# memory.net
KiCad netlist of a schematic drawn in Altium Designer
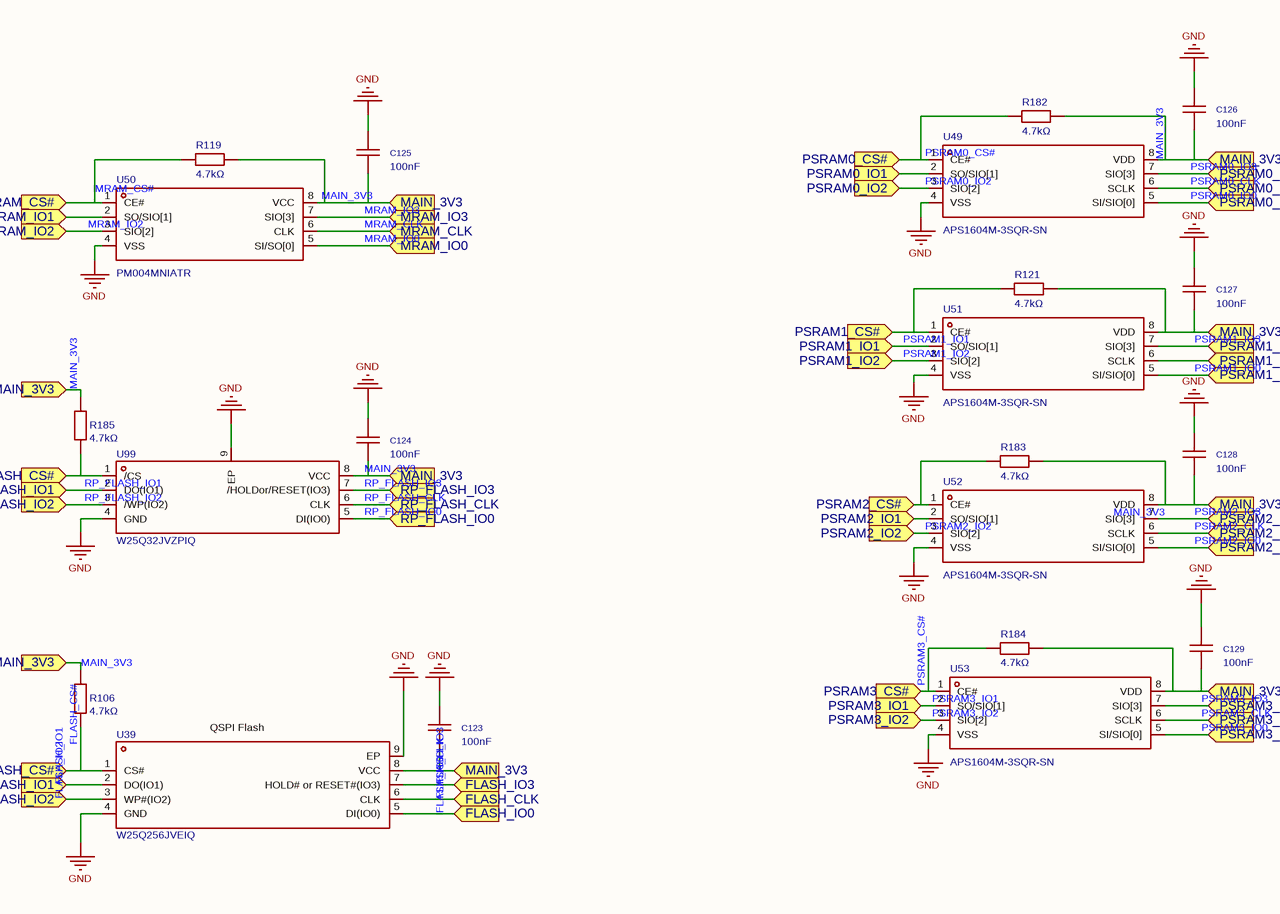
[diagram p0: memory.schdoc]

(export (version "E")
  (design (tool "Eeschema 10.0.6"))
  (components
    (comp (ref "C123")
      (value "100nF")
      (footprint "C0603")
      (description "Capacitance:22nF Tolerance:±10% Tolerance:±10% Voltage Rating:50V Temperature Coefficient:X7R")
      (fields
        (field (name "MANUFACTURER PART") "CL10B223KB8NNNC")
        (field (name "MANUFACTURER") "SAMSUNG(三星)")
      )
      (libsource (lib "altium-import") (part "root_1_CL10B223KB8NNNC_"))
    )
    (comp (ref "C124")
      (value "100nF")
      (footprint "C0603")
      (description "Capacitance:22nF Tolerance:±10% Tolerance:±10% Voltage Rating:50V Temperature Coefficient:X7R")
      (fields
        (field (name "MANUFACTURER PART") "CL10B223KB8NNNC")
        (field (name "MANUFACTURER") "SAMSUNG(三星)")
      )
      (libsource (lib "altium-import") (part "root_1_CL10B223KB8NNNC_"))
    )
    (comp (ref "C125")
      (value "100nF")
      (footprint "C0603")
      (description "Capacitance:22nF Tolerance:±10% Tolerance:±10% Voltage Rating:50V Temperature Coefficient:X7R")
      (fields
        (field (name "MANUFACTURER PART") "CL10B223KB8NNNC")
        (field (name "MANUFACTURER") "SAMSUNG(三星)")
      )
      (libsource (lib "altium-import") (part "root_1_CL10B223KB8NNNC_"))
    )
    (comp (ref "C126")
      (value "100nF")
      (footprint "C0603")
      (description "Capacitance:22nF Tolerance:±10% Tolerance:±10% Voltage Rating:50V Temperature Coefficient:X7R")
      (fields
        (field (name "MANUFACTURER PART") "CL10B223KB8NNNC")
        (field (name "MANUFACTURER") "SAMSUNG(三星)")
      )
      (libsource (lib "altium-import") (part "root_1_CL10B223KB8NNNC_"))
    )
    (comp (ref "C127")
      (value "100nF")
      (footprint "C0603")
      (description "Capacitance:22nF Tolerance:±10% Tolerance:±10% Voltage Rating:50V Temperature Coefficient:X7R")
      (fields
        (field (name "MANUFACTURER PART") "CL10B223KB8NNNC")
        (field (name "MANUFACTURER") "SAMSUNG(三星)")
      )
      (libsource (lib "altium-import") (part "root_1_CL10B223KB8NNNC_"))
    )
    (comp (ref "C128")
      (value "100nF")
      (footprint "C0603")
      (description "Capacitance:22nF Tolerance:±10% Tolerance:±10% Voltage Rating:50V Temperature Coefficient:X7R")
      (fields
        (field (name "MANUFACTURER PART") "CL10B223KB8NNNC")
        (field (name "MANUFACTURER") "SAMSUNG(三星)")
      )
      (libsource (lib "altium-import") (part "root_1_CL10B223KB8NNNC_"))
    )
    (comp (ref "C129")
      (value "100nF")
      (footprint "C0603")
      (description "Capacitance:22nF Tolerance:±10% Tolerance:±10% Voltage Rating:50V Temperature Coefficient:X7R")
      (fields
        (field (name "MANUFACTURER PART") "CL10B223KB8NNNC")
        (field (name "MANUFACTURER") "SAMSUNG(三星)")
      )
      (libsource (lib "altium-import") (part "root_1_CL10B223KB8NNNC_"))
    )
    (comp (ref "R106")
      (value "4.7kΩ")
      (footprint "R0603")
      (fields (field (name "MANUFACTURER") "YAGEO(国巨)") (field (name "MANUFACTURER PART") "RC0603FR-074K7L"))
      (libsource (lib "altium-import") (part "root_1_4.7kΩ_"))
    )
    (comp (ref "R119")
      (value "4.7kΩ")
      (footprint "R0603")
      (fields (field (name "MANUFACTURER") "YAGEO(国巨)") (field (name "MANUFACTURER PART") "RC0603FR-074K7L"))
      (libsource (lib "altium-import") (part "root_0_4.7kΩ_"))
    )
    (comp (ref "R121")
      (value "4.7kΩ")
      (footprint "R0603")
      (fields (field (name "MANUFACTURER") "YAGEO(国巨)") (field (name "MANUFACTURER PART") "RC0603FR-074K7L"))
      (libsource (lib "altium-import") (part "root_0_4.7kΩ_"))
    )
    (comp (ref "R182")
      (value "4.7kΩ")
      (footprint "R0603")
      (fields (field (name "MANUFACTURER") "YAGEO(国巨)") (field (name "MANUFACTURER PART") "RC0603FR-074K7L"))
      (libsource (lib "altium-import") (part "root_0_4.7kΩ_"))
    )
    (comp (ref "R183")
      (value "4.7kΩ")
      (footprint "R0603")
      (fields (field (name "MANUFACTURER") "YAGEO(国巨)") (field (name "MANUFACTURER PART") "RC0603FR-074K7L"))
      (libsource (lib "altium-import") (part "root_0_4.7kΩ_"))
    )
    (comp (ref "R184")
      (value "4.7kΩ")
      (footprint "R0603")
      (fields (field (name "MANUFACTURER") "YAGEO(国巨)") (field (name "MANUFACTURER PART") "RC0603FR-074K7L"))
      (libsource (lib "altium-import") (part "root_0_4.7kΩ_"))
    )
    (comp (ref "R185")
      (value "4.7kΩ")
      (footprint "R0603")
      (fields (field (name "MANUFACTURER") "YAGEO(国巨)") (field (name "MANUFACTURER PART") "RC0603FR-074K7L"))
      (libsource (lib "altium-import") (part "root_1_4.7kΩ_"))
    )
    (comp (ref "U39")
      (value "W25Q256JVEIQ")
      (footprint "WSON-8_L8.0-W6.10-P1.27-BL-EP")
      (fields (field (name "MANUFACTURER") "WINBOND(华邦)"))
      (libsource (lib "altium-import") (part "root_0_W25Q256JVEIQ_C97522_"))
    )
    (comp (ref "U49")
      (value "APS1604M-3SQR-SN")
      (footprint "SOIC-8_L4.9-W3.9-P1.27-LS6.0-BL")
      (fields (field (name "MANUFACTURER") "Apmemory"))
      (libsource (lib "altium-import") (part "root_0_APS1604M-3SQR-SN_C18214056_"))
    )
    (comp (ref "U50")
      (value "PM004MNIATR")
      (footprint "SOP-8_L4.9-W3.9-P1.27-LS6.0-BL")
      (fields (field (name "MANUFACTURER") "Siproin(上海矽朋)"))
      (libsource (lib "altium-import") (part "root_0_PM004MNIATR_"))
    )
    (comp (ref "U51")
      (value "APS1604M-3SQR-SN")
      (footprint "SOIC-8_L4.9-W3.9-P1.27-LS6.0-BL")
      (fields (field (name "MANUFACTURER") "Apmemory"))
      (libsource (lib "altium-import") (part "root_0_APS1604M-3SQR-SN_C18214056_"))
    )
    (comp (ref "U52")
      (value "APS1604M-3SQR-SN")
      (footprint "SOIC-8_L4.9-W3.9-P1.27-LS6.0-BL")
      (fields (field (name "MANUFACTURER") "Apmemory"))
      (libsource (lib "altium-import") (part "root_0_APS1604M-3SQR-SN_C18214056_"))
    )
    (comp (ref "U53")
      (value "APS1604M-3SQR-SN")
      (footprint "SOIC-8_L4.9-W3.9-P1.27-LS6.0-BL")
      (fields (field (name "MANUFACTURER") "Apmemory"))
      (libsource (lib "altium-import") (part "root_0_APS1604M-3SQR-SN_C18214056_"))
    )
    (comp (ref "U99")
      (value "W25Q32JVZPIQ")
      (footprint "WSON-8_L6.0-W5.0-P1.27-BL-EP")
      (fields (field (name "MANUFACTURER") "Winbond(华邦)"))
      (libsource (lib "altium-import") (part "root_0_W25Q32JVZPIQ_"))
    )
  )
  (nets
    (net (code "1") (name "/FLASH_CLK") (class "Default")
      (node (ref "U39") (pin "6") (pinfunction "CLK_6") (pintype "passive"))
    )
    (net (code "2") (name "/FLASH_CS#") (class "Default")
      (node (ref "R106") (pin "1") (pinfunction "1_1") (pintype "passive"))
      (node (ref "U39") (pin "1") (pinfunction "CS#_1") (pintype "passive"))
    )
    (net (code "3") (name "/FLASH_IO0") (class "Default")
      (node (ref "U39") (pin "5") (pinfunction "DI(IO0)_5") (pintype "passive"))
    )
    (net (code "4") (name "/FLASH_IO1") (class "Default")
      (node (ref "U39") (pin "2") (pinfunction "DO(IO1)_2") (pintype "passive"))
    )
    (net (code "5") (name "/FLASH_IO2") (class "Default")
      (node (ref "U39") (pin "3") (pinfunction "WP#(IO2)_3") (pintype "passive"))
    )
    (net (code "6") (name "/FLASH_IO3") (class "Default")
      (node (ref "U39") (pin "7") (pinfunction "HOLD#_or_RESET#(IO3)_7") (pintype "passive"))
    )
    (net (code "7") (name "/MAIN_3V3") (class "Default")
      (node (ref "C123") (pin "1") (pinfunction "1_1") (pintype "passive"))
      (node (ref "C124") (pin "1") (pinfunction "1_1") (pintype "passive"))
      (node (ref "C125") (pin "1") (pinfunction "1_1") (pintype "passive"))
      (node (ref "C126") (pin "1") (pinfunction "1_1") (pintype "passive"))
      (node (ref "C127") (pin "1") (pinfunction "1_1") (pintype "passive"))
      (node (ref "C128") (pin "1") (pinfunction "1_1") (pintype "passive"))
      (node (ref "C129") (pin "1") (pinfunction "1_1") (pintype "passive"))
      (node (ref "R106") (pin "2") (pinfunction "2_2") (pintype "passive"))
      (node (ref "R119") (pin "2") (pinfunction "2_2") (pintype "passive"))
      (node (ref "R121") (pin "2") (pinfunction "2_2") (pintype "passive"))
      (node (ref "R182") (pin "2") (pinfunction "2_2") (pintype "passive"))
      (node (ref "R183") (pin "2") (pinfunction "2_2") (pintype "passive"))
      (node (ref "R184") (pin "2") (pinfunction "2_2") (pintype "passive"))
      (node (ref "R185") (pin "2") (pinfunction "2_2") (pintype "passive"))
      (node (ref "U39") (pin "8") (pinfunction "VCC_8") (pintype "passive"))
      (node (ref "U49") (pin "8") (pinfunction "VDD_8") (pintype "passive"))
      (node (ref "U50") (pin "8") (pinfunction "VCC_8") (pintype "passive"))
      (node (ref "U51") (pin "8") (pinfunction "VDD_8") (pintype "passive"))
      (node (ref "U52") (pin "8") (pinfunction "VDD_8") (pintype "passive"))
      (node (ref "U53") (pin "8") (pinfunction "VDD_8") (pintype "passive"))
      (node (ref "U99") (pin "8") (pinfunction "VCC_8") (pintype "passive"))
    )
    (net (code "8") (name "/MRAM_CLK") (class "Default")
      (node (ref "U50") (pin "6") (pinfunction "CLK_6") (pintype "passive"))
    )
    (net (code "9") (name "/MRAM_CS#") (class "Default")
      (node (ref "R119") (pin "1") (pinfunction "1_1") (pintype "passive"))
      (node (ref "U50") (pin "1") (pinfunction "CE#_1") (pintype "passive"))
    )
    (net (code "10") (name "/MRAM_IO0") (class "Default")
      (node (ref "U50") (pin "5") (pinfunction "SI/SO[0]_5") (pintype "passive"))
    )
    (net (code "11") (name "/MRAM_IO1") (class "Default")
      (node (ref "U50") (pin "2") (pinfunction "SO/SIO[1]_2") (pintype "passive"))
    )
    (net (code "12") (name "/MRAM_IO2") (class "Default")
      (node (ref "U50") (pin "3") (pinfunction "SIO[2]_3") (pintype "passive"))
    )
    (net (code "13") (name "/MRAM_IO3") (class "Default")
      (node (ref "U50") (pin "7") (pinfunction "SIO[3]_7") (pintype "passive"))
    )
    (net (code "14") (name "/PSRAM0_CLK") (class "Default")
      (node (ref "U49") (pin "6") (pinfunction "SCLK_6") (pintype "passive"))
    )
    (net (code "15") (name "/PSRAM0_CS#") (class "Default")
      (node (ref "R182") (pin "1") (pinfunction "1_1") (pintype "passive"))
      (node (ref "U49") (pin "1") (pinfunction "CE#_1") (pintype "passive"))
    )
    (net (code "16") (name "/PSRAM0_IO0") (class "Default")
      (node (ref "U49") (pin "5") (pinfunction "SI/SIO[0]_5") (pintype "passive"))
    )
    (net (code "17") (name "/PSRAM0_IO1") (class "Default")
      (node (ref "U49") (pin "2") (pinfunction "SO/SIO[1]_2") (pintype "passive"))
    )
    (net (code "18") (name "/PSRAM0_IO2") (class "Default")
      (node (ref "U49") (pin "3") (pinfunction "SIO[2]_3") (pintype "passive"))
    )
    (net (code "19") (name "/PSRAM0_IO3") (class "Default")
      (node (ref "U49") (pin "7") (pinfunction "SIO[3]_7") (pintype "passive"))
    )
    (net (code "20") (name "/PSRAM1_CLK") (class "Default")
      (node (ref "U51") (pin "6") (pinfunction "SCLK_6") (pintype "passive"))
    )
    (net (code "21") (name "/PSRAM1_CS#") (class "Default")
      (node (ref "R121") (pin "1") (pinfunction "1_1") (pintype "passive"))
      (node (ref "U51") (pin "1") (pinfunction "CE#_1") (pintype "passive"))
    )
    (net (code "22") (name "/PSRAM1_IO0") (class "Default")
      (node (ref "U51") (pin "5") (pinfunction "SI/SIO[0]_5") (pintype "passive"))
    )
    (net (code "23") (name "/PSRAM1_IO1") (class "Default")
      (node (ref "U51") (pin "2") (pinfunction "SO/SIO[1]_2") (pintype "passive"))
    )
    (net (code "24") (name "/PSRAM1_IO2") (class "Default")
      (node (ref "U51") (pin "3") (pinfunction "SIO[2]_3") (pintype "passive"))
    )
    (net (code "25") (name "/PSRAM1_IO3") (class "Default")
      (node (ref "U51") (pin "7") (pinfunction "SIO[3]_7") (pintype "passive"))
    )
    (net (code "26") (name "/PSRAM2_CLK") (class "Default")
      (node (ref "U52") (pin "6") (pinfunction "SCLK_6") (pintype "passive"))
    )
    (net (code "27") (name "/PSRAM2_CS#") (class "Default")
      (node (ref "R183") (pin "1") (pinfunction "1_1") (pintype "passive"))
      (node (ref "U52") (pin "1") (pinfunction "CE#_1") (pintype "passive"))
    )
    (net (code "28") (name "/PSRAM2_IO0") (class "Default")
      (node (ref "U52") (pin "5") (pinfunction "SI/SIO[0]_5") (pintype "passive"))
    )
    (net (code "29") (name "/PSRAM2_IO1") (class "Default")
      (node (ref "U52") (pin "2") (pinfunction "SO/SIO[1]_2") (pintype "passive"))
    )
    (net (code "30") (name "/PSRAM2_IO2") (class "Default")
      (node (ref "U52") (pin "3") (pinfunction "SIO[2]_3") (pintype "passive"))
    )
    (net (code "31") (name "/PSRAM2_IO3") (class "Default")
      (node (ref "U52") (pin "7") (pinfunction "SIO[3]_7") (pintype "passive"))
    )
    (net (code "32") (name "/PSRAM3_CLK") (class "Default")
      (node (ref "U53") (pin "6") (pinfunction "SCLK_6") (pintype "passive"))
    )
    (net (code "33") (name "/PSRAM3_CS#") (class "Default")
      (node (ref "R184") (pin "1") (pinfunction "1_1") (pintype "passive"))
      (node (ref "U53") (pin "1") (pinfunction "CE#_1") (pintype "passive"))
    )
    (net (code "34") (name "/PSRAM3_IO0") (class "Default")
      (node (ref "U53") (pin "5") (pinfunction "SI/SIO[0]_5") (pintype "passive"))
    )
    (net (code "35") (name "/PSRAM3_IO1") (class "Default")
      (node (ref "U53") (pin "2") (pinfunction "SO/SIO[1]_2") (pintype "passive"))
    )
    (net (code "36") (name "/PSRAM3_IO2") (class "Default")
      (node (ref "U53") (pin "3") (pinfunction "SIO[2]_3") (pintype "passive"))
    )
    (net (code "37") (name "/PSRAM3_IO3") (class "Default")
      (node (ref "U53") (pin "7") (pinfunction "SIO[3]_7") (pintype "passive"))
    )
    (net (code "38") (name "/RP_FLASH_CLK") (class "Default")
      (node (ref "U99") (pin "6") (pinfunction "CLK_6") (pintype "passive"))
    )
    (net (code "39") (name "/RP_FLASH_CS#") (class "Default")
      (node (ref "R185") (pin "1") (pinfunction "1_1") (pintype "passive"))
      (node (ref "U99") (pin "1") (pinfunction "/CS_1") (pintype "passive"))
    )
    (net (code "40") (name "/RP_FLASH_IO0") (class "Default")
      (node (ref "U99") (pin "5") (pinfunction "DI(IO0)_5") (pintype "passive"))
    )
    (net (code "41") (name "/RP_FLASH_IO1") (class "Default")
      (node (ref "U99") (pin "2") (pinfunction "DO(IO1)_2") (pintype "passive"))
    )
    (net (code "42") (name "/RP_FLASH_IO2") (class "Default")
      (node (ref "U99") (pin "3") (pinfunction "/WP(IO2)_3") (pintype "passive"))
    )
    (net (code "43") (name "/RP_FLASH_IO3") (class "Default")
      (node (ref "U99") (pin "7") (pinfunction "/HOLDor/RESET(IO3)_7") (pintype "passive"))
    )
    (net (code "44") (name "GND") (class "Default")
      (node (ref "C123") (pin "2") (pinfunction "2_2") (pintype "passive"))
      (node (ref "C124") (pin "2") (pinfunction "2_2") (pintype "passive"))
      (node (ref "C125") (pin "2") (pinfunction "2_2") (pintype "passive"))
      (node (ref "C126") (pin "2") (pinfunction "2_2") (pintype "passive"))
      (node (ref "C127") (pin "2") (pinfunction "2_2") (pintype "passive"))
      (node (ref "C128") (pin "2") (pinfunction "2_2") (pintype "passive"))
      (node (ref "C129") (pin "2") (pinfunction "2_2") (pintype "passive"))
      (node (ref "U39") (pin "4") (pinfunction "GND_4") (pintype "passive"))
      (node (ref "U39") (pin "9") (pinfunction "EP_9") (pintype "passive"))
      (node (ref "U49") (pin "4") (pinfunction "VSS_4") (pintype "passive"))
      (node (ref "U50") (pin "4") (pinfunction "VSS_4") (pintype "passive"))
      (node (ref "U51") (pin "4") (pinfunction "VSS_4") (pintype "passive"))
      (node (ref "U52") (pin "4") (pinfunction "VSS_4") (pintype "passive"))
      (node (ref "U53") (pin "4") (pinfunction "VSS_4") (pintype "passive"))
      (node (ref "U99") (pin "4") (pinfunction "GND_4") (pintype "passive"))
      (node (ref "U99") (pin "9") (pinfunction "EP_9") (pintype "passive"))
    )
  )
)
